# MPU-Memory.net
KiCad netlist of a schematic drawn in Altium Designer
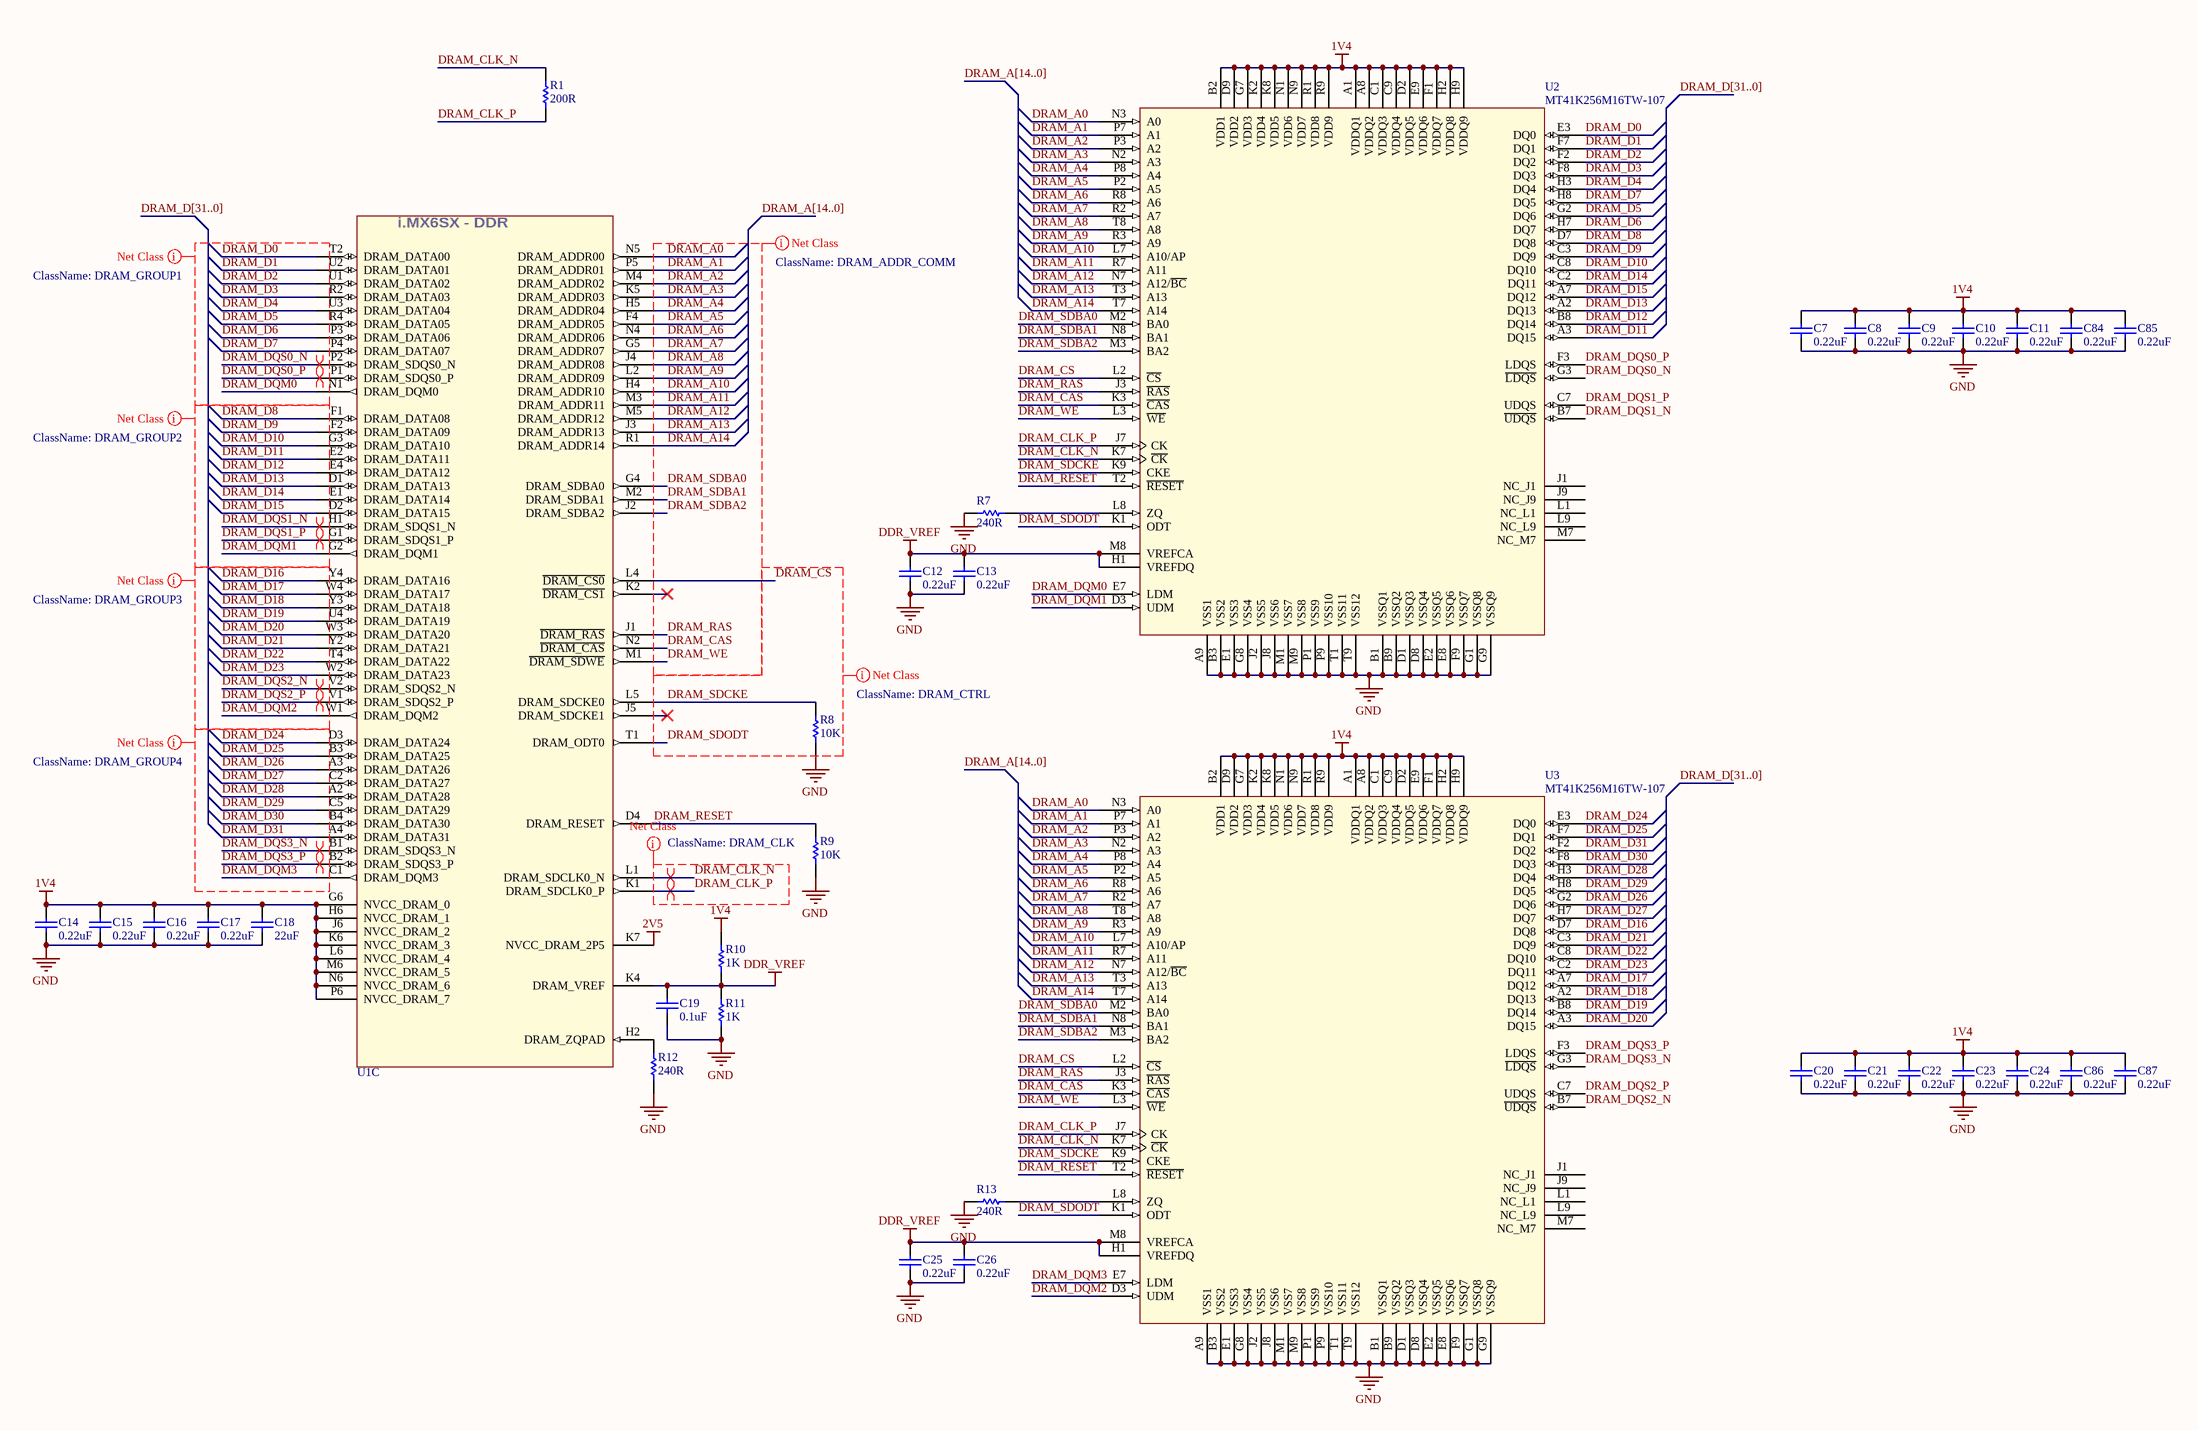
[diagram p0: MPU-Memory.SchDoc]

(export (version "E")
  (design (tool "Eeschema 10.0.6"))
  (components
    (comp (ref "C7")
      (value "0.22uF")
      (footprint "C0402[1005X55]")
      (description "0.22uF 6.3V 10% 0402 (1005 Metric)")
      (fields (field (name "PARTNUMBER") "JMK105BJ224KV-F") (field (name "MANUFACTURER") "Taiyo Yuden"))
      (libsource (lib "Capacitors") (part "CAP_0.22uF_6.3V_0402_10%"))
    )
    (comp (ref "C8")
      (value "0.22uF")
      (footprint "C0402[1005X55]")
      (description "0.22uF 6.3V 10% 0402 (1005 Metric)")
      (fields (field (name "PARTNUMBER") "JMK105BJ224KV-F") (field (name "MANUFACTURER") "Taiyo Yuden"))
      (libsource (lib "Capacitors") (part "CAP_0.22uF_6.3V_0402_10%"))
    )
    (comp (ref "C9")
      (value "0.22uF")
      (footprint "C0402[1005X55]")
      (description "0.22uF 6.3V 10% 0402 (1005 Metric)")
      (fields (field (name "PARTNUMBER") "JMK105BJ224KV-F") (field (name "MANUFACTURER") "Taiyo Yuden"))
      (libsource (lib "Capacitors") (part "CAP_0.22uF_6.3V_0402_10%"))
    )
    (comp (ref "C10")
      (value "0.22uF")
      (footprint "C0402[1005X55]")
      (description "0.22uF 6.3V 10% 0402 (1005 Metric)")
      (fields (field (name "PARTNUMBER") "JMK105BJ224KV-F") (field (name "MANUFACTURER") "Taiyo Yuden"))
      (libsource (lib "Capacitors") (part "CAP_0.22uF_6.3V_0402_10%"))
    )
    (comp (ref "C11")
      (value "0.22uF")
      (footprint "C0402[1005X55]")
      (description "0.22uF 6.3V 10% 0402 (1005 Metric)")
      (fields (field (name "PARTNUMBER") "JMK105BJ224KV-F") (field (name "MANUFACTURER") "Taiyo Yuden"))
      (libsource (lib "Capacitors") (part "CAP_0.22uF_6.3V_0402_10%"))
    )
    (comp (ref "C12")
      (value "0.22uF")
      (footprint "C0402[1005X55]")
      (description "0.22uF 6.3V 10% 0402 (1005 Metric)")
      (fields (field (name "PARTNUMBER") "JMK105BJ224KV-F") (field (name "MANUFACTURER") "Taiyo Yuden"))
      (libsource (lib "Capacitors") (part "CAP_0.22uF_6.3V_0402_10%"))
    )
    (comp (ref "C13")
      (value "0.22uF")
      (footprint "C0402[1005X55]")
      (description "0.22uF 6.3V 10% 0402 (1005 Metric)")
      (fields (field (name "PARTNUMBER") "JMK105BJ224KV-F") (field (name "MANUFACTURER") "Taiyo Yuden"))
      (libsource (lib "Capacitors") (part "CAP_0.22uF_6.3V_0402_10%"))
    )
    (comp (ref "C14")
      (value "0.22uF")
      (footprint "C0402[1005X55]")
      (description "0.22uF 6.3V 10% 0402 (1005 Metric)")
      (fields (field (name "PARTNUMBER") "JMK105BJ224KV-F") (field (name "MANUFACTURER") "Taiyo Yuden"))
      (libsource (lib "Capacitors") (part "CAP_0.22uF_6.3V_0402_10%"))
    )
    (comp (ref "C15")
      (value "0.22uF")
      (footprint "C0402[1005X55]")
      (description "0.22uF 6.3V 10% 0402 (1005 Metric)")
      (fields (field (name "PARTNUMBER") "JMK105BJ224KV-F") (field (name "MANUFACTURER") "Taiyo Yuden"))
      (libsource (lib "Capacitors") (part "CAP_0.22uF_6.3V_0402_10%"))
    )
    (comp (ref "C16")
      (value "0.22uF")
      (footprint "C0402[1005X55]")
      (description "0.22uF 6.3V 10% 0402 (1005 Metric)")
      (fields (field (name "PARTNUMBER") "JMK105BJ224KV-F") (field (name "MANUFACTURER") "Taiyo Yuden"))
      (libsource (lib "Capacitors") (part "CAP_0.22uF_6.3V_0402_10%"))
    )
    (comp (ref "C17")
      (value "0.22uF")
      (footprint "C0402[1005X55]")
      (description "0.22uF 6.3V 10% 0402 (1005 Metric)")
      (fields (field (name "PARTNUMBER") "JMK105BJ224KV-F") (field (name "MANUFACTURER") "Taiyo Yuden"))
      (libsource (lib "Capacitors") (part "CAP_0.22uF_6.3V_0402_10%"))
    )
    (comp (ref "C18")
      (value "22uF")
      (footprint "C0603[1608X92]")
      (description "22uF 6.3V 10% 0603 (1608 Metric)")
      (fields (field (name "PARTNUMBER") "GRT188R60J226ME13D") (field (name "MANUFACTURER") "Murata"))
      (libsource (lib "Capacitors") (part "CAP_22uF_6.3V_0603_10%"))
    )
    (comp (ref "C19")
      (value "0.1uF")
      (footprint "C0402[1005X55]")
      (description "0.1uF 6.3V 10% 0402 (1005 Metric)")
      (fields (field (name "PARTNUMBER") "GRM155R70J104KA01D") (field (name "MANUFACTURER") "Murata"))
      (libsource (lib "Capacitors") (part "CAP_0.1uF_6.3V_0402_10%"))
    )
    (comp (ref "C20")
      (value "0.22uF")
      (footprint "C0402[1005X55]")
      (description "0.22uF 6.3V 10% 0402 (1005 Metric)")
      (fields (field (name "PARTNUMBER") "JMK105BJ224KV-F") (field (name "MANUFACTURER") "Taiyo Yuden"))
      (libsource (lib "Capacitors") (part "CAP_0.22uF_6.3V_0402_10%"))
    )
    (comp (ref "C21")
      (value "0.22uF")
      (footprint "C0402[1005X55]")
      (description "0.22uF 6.3V 10% 0402 (1005 Metric)")
      (fields (field (name "PARTNUMBER") "JMK105BJ224KV-F") (field (name "MANUFACTURER") "Taiyo Yuden"))
      (libsource (lib "Capacitors") (part "CAP_0.22uF_6.3V_0402_10%"))
    )
    (comp (ref "C22")
      (value "0.22uF")
      (footprint "C0402[1005X55]")
      (description "0.22uF 6.3V 10% 0402 (1005 Metric)")
      (fields (field (name "PARTNUMBER") "JMK105BJ224KV-F") (field (name "MANUFACTURER") "Taiyo Yuden"))
      (libsource (lib "Capacitors") (part "CAP_0.22uF_6.3V_0402_10%"))
    )
    (comp (ref "C23")
      (value "0.22uF")
      (footprint "C0402[1005X55]")
      (description "0.22uF 6.3V 10% 0402 (1005 Metric)")
      (fields (field (name "PARTNUMBER") "JMK105BJ224KV-F") (field (name "MANUFACTURER") "Taiyo Yuden"))
      (libsource (lib "Capacitors") (part "CAP_0.22uF_6.3V_0402_10%"))
    )
    (comp (ref "C24")
      (value "0.22uF")
      (footprint "C0402[1005X55]")
      (description "0.22uF 6.3V 10% 0402 (1005 Metric)")
      (fields (field (name "PARTNUMBER") "JMK105BJ224KV-F") (field (name "MANUFACTURER") "Taiyo Yuden"))
      (libsource (lib "Capacitors") (part "CAP_0.22uF_6.3V_0402_10%"))
    )
    (comp (ref "C25")
      (value "0.22uF")
      (footprint "C0402[1005X55]")
      (description "0.22uF 6.3V 10% 0402 (1005 Metric)")
      (fields (field (name "PARTNUMBER") "JMK105BJ224KV-F") (field (name "MANUFACTURER") "Taiyo Yuden"))
      (libsource (lib "Capacitors") (part "CAP_0.22uF_6.3V_0402_10%"))
    )
    (comp (ref "C26")
      (value "0.22uF")
      (footprint "C0402[1005X55]")
      (description "0.22uF 6.3V 10% 0402 (1005 Metric)")
      (fields (field (name "PARTNUMBER") "JMK105BJ224KV-F") (field (name "MANUFACTURER") "Taiyo Yuden"))
      (libsource (lib "Capacitors") (part "CAP_0.22uF_6.3V_0402_10%"))
    )
    (comp (ref "C84")
      (value "0.22uF")
      (footprint "C0402[1005X55]")
      (description "0.22uF 6.3V 10% 0402 (1005 Metric)")
      (fields (field (name "PARTNUMBER") "JMK105BJ224KV-F") (field (name "MANUFACTURER") "Taiyo Yuden"))
      (libsource (lib "Capacitors") (part "CAP_0.22uF_6.3V_0402_10%"))
    )
    (comp (ref "C85")
      (value "0.22uF")
      (footprint "C0402[1005X55]")
      (description "0.22uF 6.3V 10% 0402 (1005 Metric)")
      (fields (field (name "PARTNUMBER") "JMK105BJ224KV-F") (field (name "MANUFACTURER") "Taiyo Yuden"))
      (libsource (lib "Capacitors") (part "CAP_0.22uF_6.3V_0402_10%"))
    )
    (comp (ref "C86")
      (value "0.22uF")
      (footprint "C0402[1005X55]")
      (description "0.22uF 6.3V 10% 0402 (1005 Metric)")
      (fields (field (name "PARTNUMBER") "JMK105BJ224KV-F") (field (name "MANUFACTURER") "Taiyo Yuden"))
      (libsource (lib "Capacitors") (part "CAP_0.22uF_6.3V_0402_10%"))
    )
    (comp (ref "C87")
      (value "0.22uF")
      (footprint "C0402[1005X55]")
      (description "0.22uF 6.3V 10% 0402 (1005 Metric)")
      (fields (field (name "PARTNUMBER") "JMK105BJ224KV-F") (field (name "MANUFACTURER") "Taiyo Yuden"))
      (libsource (lib "Capacitors") (part "CAP_0.22uF_6.3V_0402_10%"))
    )
    (comp (ref "R1")
      (value "200R")
      (footprint "R0402[1005]")
      (description "200R 0.063W 1% 0402 (1005 Metric)")
      (fields (field (name "MANUFACTURER") "KOA Speer") (field (name "PARTNUMBER") "RK73H1ETTP2000F"))
      (libsource (lib "Resistors") (part "RES_200R_0402_1%"))
    )
    (comp (ref "R7")
      (value "240R")
      (footprint "R0402[1005]")
      (description "240R 0.063W 1% 0402 (1005 Metric)")
      (fields (field (name "MANUFACTURER") "KOA Speer") (field (name "PARTNUMBER") "RK73H1ETTP2400F"))
      (libsource (lib "Resistors") (part "RES_240R_0402_1%"))
    )
    (comp (ref "R8")
      (value "10K")
      (footprint "R0402[1005]")
      (description "10K 0.063W 1% 0402 (1005 Metric)")
      (fields (field (name "MANUFACTURER") "KOA Speer") (field (name "PARTNUMBER") "RK73H1ETTP1002F"))
      (libsource (lib "Resistors") (part "RES_10K_0402_1%"))
    )
    (comp (ref "R9")
      (value "10K")
      (footprint "R0402[1005]")
      (description "10K 0.063W 1% 0402 (1005 Metric)")
      (fields (field (name "MANUFACTURER") "KOA Speer") (field (name "PARTNUMBER") "RK73H1ETTP1002F"))
      (libsource (lib "Resistors") (part "RES_10K_0402_1%"))
    )
    (comp (ref "R10")
      (value "1K")
      (footprint "R0402[1005]")
      (description "1K 0.063W 1% 0402 (1005 Metric)")
      (fields (field (name "MANUFACTURER") "KOA Speer") (field (name "PARTNUMBER") "RK73H1ETTP1001F"))
      (libsource (lib "Resistors") (part "RES_1K_0402_1%"))
    )
    (comp (ref "R11")
      (value "1K")
      (footprint "R0402[1005]")
      (description "1K 0.063W 1% 0402 (1005 Metric)")
      (fields (field (name "MANUFACTURER") "KOA Speer") (field (name "PARTNUMBER") "RK73H1ETTP1001F"))
      (libsource (lib "Resistors") (part "RES_1K_0402_1%"))
    )
    (comp (ref "R12")
      (value "240R")
      (footprint "R0402[1005]")
      (description "240R 0.063W 1% 0402 (1005 Metric)")
      (fields (field (name "MANUFACTURER") "KOA Speer") (field (name "PARTNUMBER") "RK73H1ETTP2400F"))
      (libsource (lib "Resistors") (part "RES_240R_0402_1%"))
    )
    (comp (ref "R13")
      (value "240R")
      (footprint "R0402[1005]")
      (description "240R 0.063W 1% 0402 (1005 Metric)")
      (fields (field (name "MANUFACTURER") "KOA Speer") (field (name "PARTNUMBER") "RK73H1ETTP2400F"))
      (libsource (lib "Resistors") (part "RES_240R_0402_1%"))
    )
    (comp (ref "U1")
      (value "MCIMX6X3EVO10AB")
      (footprint "BGA-400")
      (description "IC MPU I.MX6SX 1GHZ 400MAPBGA")
      (fields (field (name "MANUFACTURER") "NXP"))
      (libsource (lib "ICs") (part "MCIMX6X3EVO10AB"))
    )
    (comp (ref "U2")
      (value "MT41K256M16TW-107")
      (footprint "BGA-96")
      (description "IC SDRAM 4GBIT 933MHZ 96FBGA")
      (fields (field (name "MANUFACTURER") "Micron Technology"))
      (libsource (lib "ICs") (part "MT41K256M16TW-107"))
    )
    (comp (ref "U3")
      (value "MT41K256M16TW-107")
      (footprint "BGA-96")
      (description "IC SDRAM 4GBIT 933MHZ 96FBGA")
      (fields (field (name "MANUFACTURER") "Micron Technology"))
      (libsource (lib "ICs") (part "MT41K256M16TW-107"))
    )
  )
  (nets
    (net (code "1") (name "/DRAM_A0") (class "Default")
      (node (ref "U1") (pin "N5") (pinfunction "DRAM_ADDR00_N5") (pintype "output"))
      (node (ref "U2") (pin "N3") (pinfunction "A0_N3") (pintype "input"))
      (node (ref "U3") (pin "N3") (pinfunction "A0_N3") (pintype "input"))
    )
    (net (code "2") (name "/DRAM_A1") (class "Default")
      (node (ref "U1") (pin "P5") (pinfunction "DRAM_ADDR01_P5") (pintype "output"))
      (node (ref "U2") (pin "P7") (pinfunction "A1_P7") (pintype "input"))
      (node (ref "U3") (pin "P7") (pinfunction "A1_P7") (pintype "input"))
    )
    (net (code "3") (name "/DRAM_A2") (class "Default")
      (node (ref "U1") (pin "M4") (pinfunction "DRAM_ADDR02_M4") (pintype "output"))
      (node (ref "U2") (pin "P3") (pinfunction "A2_P3") (pintype "input"))
      (node (ref "U3") (pin "P3") (pinfunction "A2_P3") (pintype "input"))
    )
    (net (code "4") (name "/DRAM_A3") (class "Default")
      (node (ref "U1") (pin "K5") (pinfunction "DRAM_ADDR03_K5") (pintype "output"))
      (node (ref "U2") (pin "N2") (pinfunction "A3_N2") (pintype "input"))
      (node (ref "U3") (pin "N2") (pinfunction "A3_N2") (pintype "input"))
    )
    (net (code "5") (name "/DRAM_A4") (class "Default")
      (node (ref "U1") (pin "H5") (pinfunction "DRAM_ADDR04_H5") (pintype "output"))
      (node (ref "U2") (pin "P8") (pinfunction "A4_P8") (pintype "input"))
      (node (ref "U3") (pin "P8") (pinfunction "A4_P8") (pintype "input"))
    )
    (net (code "6") (name "/DRAM_A5") (class "Default")
      (node (ref "U1") (pin "F4") (pinfunction "DRAM_ADDR05_F4") (pintype "output"))
      (node (ref "U2") (pin "P2") (pinfunction "A5_P2") (pintype "input"))
      (node (ref "U3") (pin "P2") (pinfunction "A5_P2") (pintype "input"))
    )
    (net (code "7") (name "/DRAM_A6") (class "Default")
      (node (ref "U1") (pin "N4") (pinfunction "DRAM_ADDR06_N4") (pintype "output"))
      (node (ref "U2") (pin "R8") (pinfunction "A6_R8") (pintype "input"))
      (node (ref "U3") (pin "R8") (pinfunction "A6_R8") (pintype "input"))
    )
    (net (code "8") (name "/DRAM_A7") (class "Default")
      (node (ref "U1") (pin "G5") (pinfunction "DRAM_ADDR07_G5") (pintype "output"))
      (node (ref "U2") (pin "R2") (pinfunction "A7_R2") (pintype "input"))
      (node (ref "U3") (pin "R2") (pinfunction "A7_R2") (pintype "input"))
    )
    (net (code "9") (name "/DRAM_A8") (class "Default")
      (node (ref "U1") (pin "J4") (pinfunction "DRAM_ADDR08_J4") (pintype "output"))
      (node (ref "U2") (pin "T8") (pinfunction "A8_T8") (pintype "input"))
      (node (ref "U3") (pin "T8") (pinfunction "A8_T8") (pintype "input"))
    )
    (net (code "10") (name "/DRAM_A9") (class "Default")
      (node (ref "U1") (pin "L2") (pinfunction "DRAM_ADDR09_L2") (pintype "output"))
      (node (ref "U2") (pin "R3") (pinfunction "A9_R3") (pintype "input"))
      (node (ref "U3") (pin "R3") (pinfunction "A9_R3") (pintype "input"))
    )
    (net (code "11") (name "/DRAM_A10") (class "Default")
      (node (ref "U1") (pin "H4") (pinfunction "DRAM_ADDR10_H4") (pintype "output"))
      (node (ref "U2") (pin "L7") (pinfunction "A10/AP_L7") (pintype "input"))
      (node (ref "U3") (pin "L7") (pinfunction "A10/AP_L7") (pintype "input"))
    )
    (net (code "12") (name "/DRAM_A11") (class "Default")
      (node (ref "U1") (pin "M3") (pinfunction "DRAM_ADDR11_M3") (pintype "output"))
      (node (ref "U2") (pin "R7") (pinfunction "A11_R7") (pintype "input"))
      (node (ref "U3") (pin "R7") (pinfunction "A11_R7") (pintype "input"))
    )
    (net (code "13") (name "/DRAM_A12") (class "Default")
      (node (ref "U1") (pin "M5") (pinfunction "DRAM_ADDR12_M5") (pintype "output"))
      (node (ref "U2") (pin "N7") (pinfunction "A12/~{BC}_N7") (pintype "input"))
      (node (ref "U3") (pin "N7") (pinfunction "A12/~{BC}_N7") (pintype "input"))
    )
    (net (code "14") (name "/DRAM_A13") (class "Default")
      (node (ref "U1") (pin "J3") (pinfunction "DRAM_ADDR13_J3") (pintype "output"))
      (node (ref "U2") (pin "T3") (pinfunction "A13_T3") (pintype "input"))
      (node (ref "U3") (pin "T3") (pinfunction "A13_T3") (pintype "input"))
    )
    (net (code "15") (name "/DRAM_A14") (class "Default")
      (node (ref "U1") (pin "R1") (pinfunction "DRAM_ADDR14_R1") (pintype "output"))
      (node (ref "U2") (pin "T7") (pinfunction "A14_T7") (pintype "input"))
      (node (ref "U3") (pin "T7") (pinfunction "A14_T7") (pintype "input"))
    )
    (net (code "17") (name "/DRAM_CAS") (class "Default")
      (node (ref "U1") (pin "N2") (pinfunction "~{DRAM_CAS}_N2") (pintype "output"))
      (node (ref "U2") (pin "K3") (pinfunction "~{CAS}_K3") (pintype "input"))
      (node (ref "U3") (pin "K3") (pinfunction "~{CAS}_K3") (pintype "input"))
    )
    (net (code "18") (name "/DRAM_CLK_N") (class "Default")
      (node (ref "R1") (pin "2") (pinfunction "2_2") (pintype "passive"))
      (node (ref "U1") (pin "L1") (pinfunction "DRAM_SDCLK0_N_L1") (pintype "output"))
      (node (ref "U2") (pin "K7") (pinfunction "~{CK}_K7") (pintype "input"))
      (node (ref "U3") (pin "K7") (pinfunction "~{CK}_K7") (pintype "input"))
    )
    (net (code "19") (name "/DRAM_CLK_P") (class "Default")
      (node (ref "R1") (pin "1") (pinfunction "1_1") (pintype "passive"))
      (node (ref "U1") (pin "K1") (pinfunction "DRAM_SDCLK0_P_K1") (pintype "output"))
      (node (ref "U2") (pin "J7") (pinfunction "CK_J7") (pintype "input"))
      (node (ref "U3") (pin "J7") (pinfunction "CK_J7") (pintype "input"))
    )
    (net (code "20") (name "/DRAM_CS") (class "Default")
      (node (ref "U1") (pin "L4") (pinfunction "~{DRAM_CS0}_L4") (pintype "output"))
      (node (ref "U2") (pin "L2") (pinfunction "~{CS}_L2") (pintype "input"))
      (node (ref "U3") (pin "L2") (pinfunction "~{CS}_L2") (pintype "input"))
    )
    (net (code "21") (name "/DRAM_D0") (class "Default")
      (node (ref "U1") (pin "T2") (pinfunction "DRAM_DATA00_T2") (pintype "bidirectional"))
      (node (ref "U2") (pin "E3") (pinfunction "DQ0_E3") (pintype "bidirectional"))
    )
    (net (code "22") (name "/DRAM_D1") (class "Default")
      (node (ref "U1") (pin "U2") (pinfunction "DRAM_DATA01_U2") (pintype "bidirectional"))
      (node (ref "U2") (pin "F7") (pinfunction "DQ1_F7") (pintype "bidirectional"))
    )
    (net (code "23") (name "/DRAM_D2") (class "Default")
      (node (ref "U1") (pin "U1") (pinfunction "DRAM_DATA02_U1") (pintype "bidirectional"))
      (node (ref "U2") (pin "F2") (pinfunction "DQ2_F2") (pintype "bidirectional"))
    )
    (net (code "24") (name "/DRAM_D3") (class "Default")
      (node (ref "U1") (pin "R2") (pinfunction "DRAM_DATA03_R2") (pintype "bidirectional"))
      (node (ref "U2") (pin "F8") (pinfunction "DQ3_F8") (pintype "bidirectional"))
    )
    (net (code "25") (name "/DRAM_D4") (class "Default")
      (node (ref "U1") (pin "U3") (pinfunction "DRAM_DATA04_U3") (pintype "bidirectional"))
      (node (ref "U2") (pin "H3") (pinfunction "DQ4_H3") (pintype "bidirectional"))
    )
    (net (code "26") (name "/DRAM_D5") (class "Default")
      (node (ref "U1") (pin "R4") (pinfunction "DRAM_DATA05_R4") (pintype "bidirectional"))
      (node (ref "U2") (pin "G2") (pinfunction "DQ6_G2") (pintype "bidirectional"))
    )
    (net (code "27") (name "/DRAM_D6") (class "Default")
      (node (ref "U1") (pin "P3") (pinfunction "DRAM_DATA06_P3") (pintype "bidirectional"))
      (node (ref "U2") (pin "H7") (pinfunction "DQ7_H7") (pintype "bidirectional"))
    )
    (net (code "28") (name "/DRAM_D7") (class "Default")
      (node (ref "U1") (pin "P4") (pinfunction "DRAM_DATA07_P4") (pintype "bidirectional"))
      (node (ref "U2") (pin "H8") (pinfunction "DQ5_H8") (pintype "bidirectional"))
    )
    (net (code "29") (name "/DRAM_D8") (class "Default")
      (node (ref "U1") (pin "F1") (pinfunction "DRAM_DATA08_F1") (pintype "bidirectional"))
      (node (ref "U2") (pin "D7") (pinfunction "DQ8_D7") (pintype "bidirectional"))
    )
    (net (code "30") (name "/DRAM_D9") (class "Default")
      (node (ref "U1") (pin "F2") (pinfunction "DRAM_DATA09_F2") (pintype "bidirectional"))
      (node (ref "U2") (pin "C3") (pinfunction "DQ9_C3") (pintype "bidirectional"))
    )
    (net (code "31") (name "/DRAM_D10") (class "Default")
      (node (ref "U1") (pin "G3") (pinfunction "DRAM_DATA10_G3") (pintype "bidirectional"))
      (node (ref "U2") (pin "C8") (pinfunction "DQ10_C8") (pintype "bidirectional"))
    )
    (net (code "32") (name "/DRAM_D11") (class "Default")
      (node (ref "U1") (pin "E2") (pinfunction "DRAM_DATA11_E2") (pintype "bidirectional"))
      (node (ref "U2") (pin "A3") (pinfunction "DQ15_A3") (pintype "bidirectional"))
    )
    (net (code "33") (name "/DRAM_D12") (class "Default")
      (node (ref "U1") (pin "E4") (pinfunction "DRAM_DATA12_E4") (pintype "bidirectional"))
      (node (ref "U2") (pin "B8") (pinfunction "DQ14_B8") (pintype "bidirectional"))
    )
    (net (code "34") (name "/DRAM_D13") (class "Default")
      (node (ref "U1") (pin "D1") (pinfunction "DRAM_DATA13_D1") (pintype "bidirectional"))
      (node (ref "U2") (pin "A2") (pinfunction "DQ13_A2") (pintype "bidirectional"))
    )
    (net (code "35") (name "/DRAM_D14") (class "Default")
      (node (ref "U1") (pin "E1") (pinfunction "DRAM_DATA14_E1") (pintype "bidirectional"))
      (node (ref "U2") (pin "C2") (pinfunction "DQ11_C2") (pintype "bidirectional"))
    )
    (net (code "36") (name "/DRAM_D15") (class "Default")
      (node (ref "U1") (pin "D2") (pinfunction "DRAM_DATA15_D2") (pintype "bidirectional"))
      (node (ref "U2") (pin "A7") (pinfunction "DQ12_A7") (pintype "bidirectional"))
    )
    (net (code "37") (name "/DRAM_D16") (class "Default")
      (node (ref "U1") (pin "Y4") (pinfunction "DRAM_DATA16_Y4") (pintype "bidirectional"))
      (node (ref "U3") (pin "D7") (pinfunction "DQ8_D7") (pintype "bidirectional"))
    )
    (net (code "38") (name "/DRAM_D17") (class "Default")
      (node (ref "U1") (pin "W4") (pinfunction "DRAM_DATA17_W4") (pintype "bidirectional"))
      (node (ref "U3") (pin "A7") (pinfunction "DQ12_A7") (pintype "bidirectional"))
    )
    (net (code "39") (name "/DRAM_D18") (class "Default")
      (node (ref "U1") (pin "Y3") (pinfunction "DRAM_DATA18_Y3") (pintype "bidirectional"))
      (node (ref "U3") (pin "A2") (pinfunction "DQ13_A2") (pintype "bidirectional"))
    )
    (net (code "40") (name "/DRAM_D19") (class "Default")
      (node (ref "U1") (pin "U4") (pinfunction "DRAM_DATA19_U4") (pintype "bidirectional"))
      (node (ref "U3") (pin "B8") (pinfunction "DQ14_B8") (pintype "bidirectional"))
    )
    (net (code "41") (name "/DRAM_D20") (class "Default")
      (node (ref "U1") (pin "W3") (pinfunction "DRAM_DATA20_W3") (pintype "bidirectional"))
      (node (ref "U3") (pin "A3") (pinfunction "DQ15_A3") (pintype "bidirectional"))
    )
    (net (code "42") (name "/DRAM_D21") (class "Default")
      (node (ref "U1") (pin "Y2") (pinfunction "DRAM_DATA21_Y2") (pintype "bidirectional"))
      (node (ref "U3") (pin "C3") (pinfunction "DQ9_C3") (pintype "bidirectional"))
    )
    (net (code "43") (name "/DRAM_D22") (class "Default")
      (node (ref "U1") (pin "T4") (pinfunction "DRAM_DATA22_T4") (pintype "bidirectional"))
      (node (ref "U3") (pin "C8") (pinfunction "DQ10_C8") (pintype "bidirectional"))
    )
    (net (code "44") (name "/DRAM_D23") (class "Default")
      (node (ref "U1") (pin "W2") (pinfunction "DRAM_DATA23_W2") (pintype "bidirectional"))
      (node (ref "U3") (pin "C2") (pinfunction "DQ11_C2") (pintype "bidirectional"))
    )
    (net (code "45") (name "/DRAM_D24") (class "Default")
      (node (ref "U1") (pin "D3") (pinfunction "DRAM_DATA24_D3") (pintype "bidirectional"))
      (node (ref "U3") (pin "E3") (pinfunction "DQ0_E3") (pintype "bidirectional"))
    )
    (net (code "46") (name "/DRAM_D25") (class "Default")
      (node (ref "U1") (pin "B3") (pinfunction "DRAM_DATA25_B3") (pintype "bidirectional"))
      (node (ref "U3") (pin "F7") (pinfunction "DQ1_F7") (pintype "bidirectional"))
    )
    (net (code "47") (name "/DRAM_D26") (class "Default")
      (node (ref "U1") (pin "A3") (pinfunction "DRAM_DATA26_A3") (pintype "bidirectional"))
      (node (ref "U3") (pin "G2") (pinfunction "DQ6_G2") (pintype "bidirectional"))
    )
    (net (code "48") (name "/DRAM_D27") (class "Default")
      (node (ref "U1") (pin "C2") (pinfunction "DRAM_DATA27_C2") (pintype "bidirectional"))
      (node (ref "U3") (pin "H7") (pinfunction "DQ7_H7") (pintype "bidirectional"))
    )
    (net (code "49") (name "/DRAM_D28") (class "Default")
      (node (ref "U1") (pin "A2") (pinfunction "DRAM_DATA28_A2") (pintype "bidirectional"))
      (node (ref "U3") (pin "H3") (pinfunction "DQ4_H3") (pintype "bidirectional"))
    )
    (net (code "50") (name "/DRAM_D29") (class "Default")
      (node (ref "U1") (pin "C5") (pinfunction "DRAM_DATA29_C5") (pintype "bidirectional"))
      (node (ref "U3") (pin "H8") (pinfunction "DQ5_H8") (pintype "bidirectional"))
    )
    (net (code "51") (name "/DRAM_D30") (class "Default")
      (node (ref "U1") (pin "B4") (pinfunction "DRAM_DATA30_B4") (pintype "bidirectional"))
      (node (ref "U3") (pin "F8") (pinfunction "DQ3_F8") (pintype "bidirectional"))
    )
    (net (code "52") (name "/DRAM_D31") (class "Default")
      (node (ref "U1") (pin "A4") (pinfunction "DRAM_DATA31_A4") (pintype "bidirectional"))
      (node (ref "U3") (pin "F2") (pinfunction "DQ2_F2") (pintype "bidirectional"))
    )
    (net (code "53") (name "/DRAM_DQM0") (class "Default")
      (node (ref "U1") (pin "N1") (pinfunction "DRAM_DQM0_N1") (pintype "output"))
      (node (ref "U2") (pin "E7") (pinfunction "LDM_E7") (pintype "input"))
    )
    (net (code "54") (name "/DRAM_DQM1") (class "Default")
      (node (ref "U1") (pin "G2") (pinfunction "DRAM_DQM1_G2") (pintype "output"))
      (node (ref "U2") (pin "D3") (pinfunction "UDM_D3") (pintype "input"))
    )
    (net (code "55") (name "/DRAM_DQM2") (class "Default")
      (node (ref "U1") (pin "W1") (pinfunction "DRAM_DQM2_W1") (pintype "output"))
      (node (ref "U3") (pin "D3") (pinfunction "UDM_D3") (pintype "input"))
    )
    (net (code "56") (name "/DRAM_DQM3") (class "Default")
      (node (ref "U1") (pin "C1") (pinfunction "DRAM_DQM3_C1") (pintype "output"))
      (node (ref "U3") (pin "E7") (pinfunction "LDM_E7") (pintype "input"))
    )
    (net (code "57") (name "/DRAM_DQS0_N") (class "Default")
      (node (ref "U1") (pin "P2") (pinfunction "DRAM_SDQS0_N_P2") (pintype "bidirectional"))
      (node (ref "U2") (pin "G3") (pinfunction "~{LDQS}_G3") (pintype "bidirectional"))
    )
    (net (code "58") (name "/DRAM_DQS0_P") (class "Default")
      (node (ref "U1") (pin "P1") (pinfunction "DRAM_SDQS0_P_P1") (pintype "bidirectional"))
      (node (ref "U2") (pin "F3") (pinfunction "LDQS_F3") (pintype "bidirectional"))
    )
    (net (code "59") (name "/DRAM_DQS1_N") (class "Default")
      (node (ref "U1") (pin "H1") (pinfunction "DRAM_SDQS1_N_H1") (pintype "bidirectional"))
      (node (ref "U2") (pin "B7") (pinfunction "~{UDQS}_B7") (pintype "bidirectional"))
    )
    (net (code "60") (name "/DRAM_DQS1_P") (class "Default")
      (node (ref "U1") (pin "G1") (pinfunction "DRAM_SDQS1_P_G1") (pintype "bidirectional"))
      (node (ref "U2") (pin "C7") (pinfunction "UDQS_C7") (pintype "bidirectional"))
    )
    (net (code "61") (name "/DRAM_DQS2_N") (class "Default")
      (node (ref "U1") (pin "V2") (pinfunction "DRAM_SDQS2_N_V2") (pintype "bidirectional"))
      (node (ref "U3") (pin "B7") (pinfunction "~{UDQS}_B7") (pintype "bidirectional"))
    )
    (net (code "62") (name "/DRAM_DQS2_P") (class "Default")
      (node (ref "U1") (pin "V1") (pinfunction "DRAM_SDQS2_P_V1") (pintype "bidirectional"))
      (node (ref "U3") (pin "C7") (pinfunction "UDQS_C7") (pintype "bidirectional"))
    )
    (net (code "63") (name "/DRAM_DQS3_N") (class "Default")
      (node (ref "U1") (pin "B1") (pinfunction "DRAM_SDQS3_N_B1") (pintype "bidirectional"))
      (node (ref "U3") (pin "G3") (pinfunction "~{LDQS}_G3") (pintype "bidirectional"))
    )
    (net (code "64") (name "/DRAM_DQS3_P") (class "Default")
      (node (ref "U1") (pin "B2") (pinfunction "DRAM_SDQS3_P_B2") (pintype "bidirectional"))
      (node (ref "U3") (pin "F3") (pinfunction "LDQS_F3") (pintype "bidirectional"))
    )
    (net (code "66") (name "/DRAM_RAS") (class "Default")
      (node (ref "U1") (pin "J1") (pinfunction "~{DRAM_RAS}_J1") (pintype "output"))
      (node (ref "U2") (pin "J3") (pinfunction "~{RAS}_J3") (pintype "input"))
      (node (ref "U3") (pin "J3") (pinfunction "~{RAS}_J3") (pintype "input"))
    )
    (net (code "67") (name "/DRAM_RESET") (class "Default")
      (node (ref "R9") (pin "2") (pinfunction "2_2") (pintype "passive"))
      (node (ref "U1") (pin "D4") (pinfunction "DRAM_RESET_D4") (pintype "output"))
      (node (ref "U2") (pin "T2") (pinfunction "~{RESET}_T2") (pintype "input"))
      (node (ref "U3") (pin "T2") (pinfunction "~{RESET}_T2") (pintype "input"))
    )
    (net (code "68") (name "/DRAM_SDBA0") (class "Default")
      (node (ref "U1") (pin "G4") (pinfunction "DRAM_SDBA0_G4") (pintype "output"))
      (node (ref "U2") (pin "M2") (pinfunction "BA0_M2") (pintype "input"))
      (node (ref "U3") (pin "M2") (pinfunction "BA0_M2") (pintype "input"))
    )
    (net (code "69") (name "/DRAM_SDBA1") (class "Default")
      (node (ref "U1") (pin "M2") (pinfunction "DRAM_SDBA1_M2") (pintype "output"))
      (node (ref "U2") (pin "N8") (pinfunction "BA1_N8") (pintype "input"))
      (node (ref "U3") (pin "N8") (pinfunction "BA1_N8") (pintype "input"))
    )
    (net (code "70") (name "/DRAM_SDBA2") (class "Default")
      (node (ref "U1") (pin "J2") (pinfunction "DRAM_SDBA2_J2") (pintype "output"))
      (node (ref "U2") (pin "M3") (pinfunction "BA2_M3") (pintype "input"))
      (node (ref "U3") (pin "M3") (pinfunction "BA2_M3") (pintype "input"))
    )
    (net (code "71") (name "/DRAM_SDCKE") (class "Default")
      (node (ref "R8") (pin "2") (pinfunction "2_2") (pintype "passive"))
      (node (ref "U1") (pin "L5") (pinfunction "DRAM_SDCKE0_L5") (pintype "output"))
      (node (ref "U2") (pin "K9") (pinfunction "CKE_K9") (pintype "input"))
      (node (ref "U3") (pin "K9") (pinfunction "CKE_K9") (pintype "input"))
    )
    (net (code "72") (name "/DRAM_SDODT") (class "Default")
      (node (ref "U1") (pin "T1") (pinfunction "DRAM_ODT0_T1") (pintype "output"))
      (node (ref "U2") (pin "K1") (pinfunction "ODT_K1") (pintype "input"))
      (node (ref "U3") (pin "K1") (pinfunction "ODT_K1") (pintype "input"))
    )
    (net (code "73") (name "/DRAM_WE") (class "Default")
      (node (ref "U1") (pin "M1") (pinfunction "~{DRAM_SDWE}_M1") (pintype "output"))
      (node (ref "U2") (pin "L3") (pinfunction "~{WE}_L3") (pintype "input"))
      (node (ref "U3") (pin "L3") (pinfunction "~{WE}_L3") (pintype "input"))
    )
    (net (code "74") (name "1V4") (class "Default")
      (node (ref "C10") (pin "2") (pinfunction "2_2") (pintype "passive"))
      (node (ref "C11") (pin "2") (pinfunction "2_2") (pintype "passive"))
      (node (ref "C14") (pin "2") (pinfunction "2_2") (pintype "passive"))
      (node (ref "C15") (pin "2") (pinfunction "2_2") (pintype "passive"))
      (node (ref "C16") (pin "2") (pinfunction "2_2") (pintype "passive"))
      (node (ref "C17") (pin "2") (pinfunction "2_2") (pintype "passive"))
      (node (ref "C18") (pin "2") (pinfunction "2_2") (pintype "passive"))
      (node (ref "C20") (pin "2") (pinfunction "2_2") (pintype "passive"))
      (node (ref "C21") (pin "2") (pinfunction "2_2") (pintype "passive"))
      (node (ref "C22") (pin "2") (pinfunction "2_2") (pintype "passive"))
      (node (ref "C23") (pin "2") (pinfunction "2_2") (pintype "passive"))
      (node (ref "C24") (pin "2") (pinfunction "2_2") (pintype "passive"))
      (node (ref "C7") (pin "2") (pinfunction "2_2") (pintype "passive"))
      (node (ref "C8") (pin "2") (pinfunction "2_2") (pintype "passive"))
      (node (ref "C84") (pin "2") (pinfunction "2_2") (pintype "passive"))
      (node (ref "C85") (pin "2") (pinfunction "2_2") (pintype "passive"))
      (node (ref "C86") (pin "2") (pinfunction "2_2") (pintype "passive"))
      (node (ref "C87") (pin "2") (pinfunction "2_2") (pintype "passive"))
      (node (ref "C9") (pin "2") (pinfunction "2_2") (pintype "passive"))
      (node (ref "R10") (pin "2") (pinfunction "2_2") (pintype "passive"))
      (node (ref "U1") (pin "G6") (pinfunction "NVCC_DRAM_0_G6") (pintype "power_in"))
      (node (ref "U1") (pin "H6") (pinfunction "NVCC_DRAM_1_H6") (pintype "power_in"))
      (node (ref "U1") (pin "J6") (pinfunction "NVCC_DRAM_2_J6") (pintype "power_in"))
      (node (ref "U1") (pin "K6") (pinfunction "NVCC_DRAM_3_K6") (pintype "power_in"))
      (node (ref "U1") (pin "L6") (pinfunction "NVCC_DRAM_4_L6") (pintype "power_in"))
      (node (ref "U1") (pin "M6") (pinfunction "NVCC_DRAM_5_M6") (pintype "power_in"))
      (node (ref "U1") (pin "N6") (pinfunction "NVCC_DRAM_6_N6") (pintype "power_in"))
      (node (ref "U1") (pin "P6") (pinfunction "NVCC_DRAM_7_P6") (pintype "power_in"))
      (node (ref "U2") (pin "A1") (pinfunction "VDDQ1_A1") (pintype "power_in"))
      (node (ref "U2") (pin "A8") (pinfunction "VDDQ2_A8") (pintype "power_in"))
      (node (ref "U2") (pin "B2") (pinfunction "VDD1_B2") (pintype "power_in"))
      (node (ref "U2") (pin "C1") (pinfunction "VDDQ3_C1") (pintype "power_in"))
      (node (ref "U2") (pin "C9") (pinfunction "VDDQ4_C9") (pintype "power_in"))
      (node (ref "U2") (pin "D2") (pinfunction "VDDQ5_D2") (pintype "power_in"))
      (node (ref "U2") (pin "D9") (pinfunction "VDD2_D9") (pintype "power_in"))
      (node (ref "U2") (pin "E9") (pinfunction "VDDQ6_E9") (pintype "power_in"))
      (node (ref "U2") (pin "F1") (pinfunction "VDDQ7_F1") (pintype "power_in"))
      (node (ref "U2") (pin "G7") (pinfunction "VDD3_G7") (pintype "power_in"))
      (node (ref "U2") (pin "H2") (pinfunction "VDDQ8_H2") (pintype "power_in"))
      (node (ref "U2") (pin "H9") (pinfunction "VDDQ9_H9") (pintype "power_in"))
      (node (ref "U2") (pin "K2") (pinfunction "VDD4_K2") (pintype "power_in"))
      (node (ref "U2") (pin "K8") (pinfunction "VDD5_K8") (pintype "power_in"))
      (node (ref "U2") (pin "N1") (pinfunction "VDD6_N1") (pintype "power_in"))
      (node (ref "U2") (pin "N9") (pinfunction "VDD7_N9") (pintype "power_in"))
      (node (ref "U2") (pin "R1") (pinfunction "VDD8_R1") (pintype "power_in"))
      (node (ref "U2") (pin "R9") (pinfunction "VDD9_R9") (pintype "power_in"))
      (node (ref "U3") (pin "A1") (pinfunction "VDDQ1_A1") (pintype "power_in"))
      (node (ref "U3") (pin "A8") (pinfunction "VDDQ2_A8") (pintype "power_in"))
      (node (ref "U3") (pin "B2") (pinfunction "VDD1_B2") (pintype "power_in"))
      (node (ref "U3") (pin "C1") (pinfunction "VDDQ3_C1") (pintype "power_in"))
      (node (ref "U3") (pin "C9") (pinfunction "VDDQ4_C9") (pintype "power_in"))
      (node (ref "U3") (pin "D2") (pinfunction "VDDQ5_D2") (pintype "power_in"))
      (node (ref "U3") (pin "D9") (pinfunction "VDD2_D9") (pintype "power_in"))
      (node (ref "U3") (pin "E9") (pinfunction "VDDQ6_E9") (pintype "power_in"))
      (node (ref "U3") (pin "F1") (pinfunction "VDDQ7_F1") (pintype "power_in"))
      (node (ref "U3") (pin "G7") (pinfunction "VDD3_G7") (pintype "power_in"))
      (node (ref "U3") (pin "H2") (pinfunction "VDDQ8_H2") (pintype "power_in"))
      (node (ref "U3") (pin "H9") (pinfunction "VDDQ9_H9") (pintype "power_in"))
      (node (ref "U3") (pin "K2") (pinfunction "VDD4_K2") (pintype "power_in"))
      (node (ref "U3") (pin "K8") (pinfunction "VDD5_K8") (pintype "power_in"))
      (node (ref "U3") (pin "N1") (pinfunction "VDD6_N1") (pintype "power_in"))
      (node (ref "U3") (pin "N9") (pinfunction "VDD7_N9") (pintype "power_in"))
      (node (ref "U3") (pin "R1") (pinfunction "VDD8_R1") (pintype "power_in"))
      (node (ref "U3") (pin "R9") (pinfunction "VDD9_R9") (pintype "power_in"))
    )
    (net (code "75") (name "2V5") (class "Default")
      (node (ref "U1") (pin "K7") (pinfunction "NVCC_DRAM_2P5_K7") (pintype "power_in"))
    )
    (net (code "76") (name "DDR_VREF") (class "Default")
      (node (ref "C12") (pin "2") (pinfunction "2_2") (pintype "passive"))
      (node (ref "C13") (pin "2") (pinfunction "2_2") (pintype "passive"))
      (node (ref "C19") (pin "2") (pinfunction "2_2") (pintype "passive"))
      (node (ref "C25") (pin "2") (pinfunction "2_2") (pintype "passive"))
      (node (ref "C26") (pin "2") (pinfunction "2_2") (pintype "passive"))
      (node (ref "R10") (pin "1") (pinfunction "1_1") (pintype "passive"))
      (node (ref "R11") (pin "2") (pinfunction "2_2") (pintype "passive"))
      (node (ref "U1") (pin "K4") (pinfunction "DRAM_VREF_K4") (pintype "power_in"))
      (node (ref "U2") (pin "H1") (pinfunction "VREFDQ_H1") (pintype "power_in"))
      (node (ref "U2") (pin "M8") (pinfunction "VREFCA_M8") (pintype "power_in"))
      (node (ref "U3") (pin "H1") (pinfunction "VREFDQ_H1") (pintype "power_in"))
      (node (ref "U3") (pin "M8") (pinfunction "VREFCA_M8") (pintype "power_in"))
    )
    (net (code "77") (name "GND") (class "Default")
      (node (ref "C10") (pin "1") (pinfunction "1_1") (pintype "passive"))
      (node (ref "C11") (pin "1") (pinfunction "1_1") (pintype "passive"))
      (node (ref "C12") (pin "1") (pinfunction "1_1") (pintype "passive"))
      (node (ref "C13") (pin "1") (pinfunction "1_1") (pintype "passive"))
      (node (ref "C14") (pin "1") (pinfunction "1_1") (pintype "passive"))
      (node (ref "C15") (pin "1") (pinfunction "1_1") (pintype "passive"))
      (node (ref "C16") (pin "1") (pinfunction "1_1") (pintype "passive"))
      (node (ref "C17") (pin "1") (pinfunction "1_1") (pintype "passive"))
      (node (ref "C18") (pin "1") (pinfunction "1_1") (pintype "passive"))
      (node (ref "C19") (pin "1") (pinfunction "1_1") (pintype "passive"))
      (node (ref "C20") (pin "1") (pinfunction "1_1") (pintype "passive"))
      (node (ref "C21") (pin "1") (pinfunction "1_1") (pintype "passive"))
      (node (ref "C22") (pin "1") (pinfunction "1_1") (pintype "passive"))
      (node (ref "C23") (pin "1") (pinfunction "1_1") (pintype "passive"))
      (node (ref "C24") (pin "1") (pinfunction "1_1") (pintype "passive"))
      (node (ref "C25") (pin "1") (pinfunction "1_1") (pintype "passive"))
      (node (ref "C26") (pin "1") (pinfunction "1_1") (pintype "passive"))
      (node (ref "C7") (pin "1") (pinfunction "1_1") (pintype "passive"))
      (node (ref "C8") (pin "1") (pinfunction "1_1") (pintype "passive"))
      (node (ref "C84") (pin "1") (pinfunction "1_1") (pintype "passive"))
      (node (ref "C85") (pin "1") (pinfunction "1_1") (pintype "passive"))
      (node (ref "C86") (pin "1") (pinfunction "1_1") (pintype "passive"))
      (node (ref "C87") (pin "1") (pinfunction "1_1") (pintype "passive"))
      (node (ref "C9") (pin "1") (pinfunction "1_1") (pintype "passive"))
      (node (ref "R11") (pin "1") (pinfunction "1_1") (pintype "passive"))
      (node (ref "R12") (pin "1") (pinfunction "1_1") (pintype "passive"))
      (node (ref "R13") (pin "2") (pinfunction "2_2") (pintype "passive"))
      (node (ref "R7") (pin "2") (pinfunction "2_2") (pintype "passive"))
      (node (ref "R8") (pin "1") (pinfunction "1_1") (pintype "passive"))
      (node (ref "R9") (pin "1") (pinfunction "1_1") (pintype "passive"))
      (node (ref "U2") (pin "A9") (pinfunction "VSS1_A9") (pintype "power_in"))
      (node (ref "U2") (pin "B1") (pinfunction "VSSQ1_B1") (pintype "power_in"))
      (node (ref "U2") (pin "B3") (pinfunction "VSS2_B3") (pintype "power_in"))
      (node (ref "U2") (pin "B9") (pinfunction "VSSQ2_B9") (pintype "power_in"))
      (node (ref "U2") (pin "D1") (pinfunction "VSSQ3_D1") (pintype "power_in"))
      (node (ref "U2") (pin "D8") (pinfunction "VSSQ4_D8") (pintype "power_in"))
      (node (ref "U2") (pin "E1") (pinfunction "VSS3_E1") (pintype "power_in"))
      (node (ref "U2") (pin "E2") (pinfunction "VSSQ5_E2") (pintype "power_in"))
      (node (ref "U2") (pin "E8") (pinfunction "VSSQ6_E8") (pintype "power_in"))
      (node (ref "U2") (pin "F9") (pinfunction "VSSQ7_F9") (pintype "power_in"))
      (node (ref "U2") (pin "G1") (pinfunction "VSSQ8_G1") (pintype "power_in"))
      (node (ref "U2") (pin "G8") (pinfunction "VSS4_G8") (pintype "power_in"))
      (node (ref "U2") (pin "G9") (pinfunction "VSSQ9_G9") (pintype "power_in"))
      (node (ref "U2") (pin "J2") (pinfunction "VSS5_J2") (pintype "power_in"))
      (node (ref "U2") (pin "J8") (pinfunction "VSS6_J8") (pintype "power_in"))
      (node (ref "U2") (pin "M1") (pinfunction "VSS7_M1") (pintype "power_in"))
      (node (ref "U2") (pin "M9") (pinfunction "VSS8_M9") (pintype "power_in"))
      (node (ref "U2") (pin "P1") (pinfunction "VSS9_P1") (pintype "power_in"))
      (node (ref "U2") (pin "P9") (pinfunction "VSS10_P9") (pintype "power_in"))
      (node (ref "U2") (pin "T1") (pinfunction "VSS11_T1") (pintype "power_in"))
      (node (ref "U2") (pin "T9") (pinfunction "VSS12_T9") (pintype "power_in"))
      (node (ref "U3") (pin "A9") (pinfunction "VSS1_A9") (pintype "power_in"))
      (node (ref "U3") (pin "B1") (pinfunction "VSSQ1_B1") (pintype "power_in"))
      (node (ref "U3") (pin "B3") (pinfunction "VSS2_B3") (pintype "power_in"))
      (node (ref "U3") (pin "B9") (pinfunction "VSSQ2_B9") (pintype "power_in"))
      (node (ref "U3") (pin "D1") (pinfunction "VSSQ3_D1") (pintype "power_in"))
      (node (ref "U3") (pin "D8") (pinfunction "VSSQ4_D8") (pintype "power_in"))
      (node (ref "U3") (pin "E1") (pinfunction "VSS3_E1") (pintype "power_in"))
      (node (ref "U3") (pin "E2") (pinfunction "VSSQ5_E2") (pintype "power_in"))
      (node (ref "U3") (pin "E8") (pinfunction "VSSQ6_E8") (pintype "power_in"))
      (node (ref "U3") (pin "F9") (pinfunction "VSSQ7_F9") (pintype "power_in"))
      (node (ref "U3") (pin "G1") (pinfunction "VSSQ8_G1") (pintype "power_in"))
      (node (ref "U3") (pin "G8") (pinfunction "VSS4_G8") (pintype "power_in"))
      (node (ref "U3") (pin "G9") (pinfunction "VSSQ9_G9") (pintype "power_in"))
      (node (ref "U3") (pin "J2") (pinfunction "VSS5_J2") (pintype "power_in"))
      (node (ref "U3") (pin "J8") (pinfunction "VSS6_J8") (pintype "power_in"))
      (node (ref "U3") (pin "M1") (pinfunction "VSS7_M1") (pintype "power_in"))
      (node (ref "U3") (pin "M9") (pinfunction "VSS8_M9") (pintype "power_in"))
      (node (ref "U3") (pin "P1") (pinfunction "VSS9_P1") (pintype "power_in"))
      (node (ref "U3") (pin "P9") (pinfunction "VSS10_P9") (pintype "power_in"))
      (node (ref "U3") (pin "T1") (pinfunction "VSS11_T1") (pintype "power_in"))
      (node (ref "U3") (pin "T9") (pinfunction "VSS12_T9") (pintype "power_in"))
    )
    (net (code "78") (name "Net-(U1C-DRAM_ZQPAD)") (class "Default")
      (node (ref "R12") (pin "2") (pinfunction "2_2") (pintype "passive"))
      (node (ref "U1") (pin "H2") (pinfunction "DRAM_ZQPAD_H2") (pintype "input"))
    )
    (net (code "79") (name "Net-(U2-ZQ)") (class "Default")
      (node (ref "R7") (pin "1") (pinfunction "1_1") (pintype "passive"))
      (node (ref "U2") (pin "L8") (pinfunction "ZQ_L8") (pintype "input"))
    )
    (net (code "80") (name "Net-(U3-ZQ)") (class "Default")
      (node (ref "R13") (pin "1") (pinfunction "1_1") (pintype "passive"))
      (node (ref "U3") (pin "L8") (pinfunction "ZQ_L8") (pintype "input"))
    )
    (net (code "81") (name "unconnected-(U1C-DRAM_SDCKE1-PadJ5)") (class "Default")
      (node (ref "U1") (pin "J5") (pinfunction "DRAM_SDCKE1_J5") (pintype "output+no_connect"))
    )
    (net (code "82") (name "unconnected-(U1C-~{DRAM_CS1}-PadK2)") (class "Default")
      (node (ref "U1") (pin "K2") (pinfunction "~{DRAM_CS1}_K2") (pintype "output+no_connect"))
    )
    (net (code "83") (name "unconnected-(U2-NC_J1-PadJ1)") (class "Default")
      (node (ref "U2") (pin "J1") (pinfunction "NC_J1_J1") (pintype "passive"))
    )
    (net (code "84") (name "unconnected-(U2-NC_J9-PadJ9)") (class "Default")
      (node (ref "U2") (pin "J9") (pinfunction "NC_J9_J9") (pintype "passive"))
    )
    (net (code "85") (name "unconnected-(U2-NC_L1-PadL1)") (class "Default")
      (node (ref "U2") (pin "L1") (pinfunction "NC_L1_L1") (pintype "passive"))
    )
    (net (code "86") (name "unconnected-(U2-NC_L9-PadL9)") (class "Default")
      (node (ref "U2") (pin "L9") (pinfunction "NC_L9_L9") (pintype "passive"))
    )
    (net (code "87") (name "unconnected-(U2-NC_M7-PadM7)") (class "Default")
      (node (ref "U2") (pin "M7") (pinfunction "NC_M7_M7") (pintype "passive"))
    )
    (net (code "88") (name "unconnected-(U3-NC_J1-PadJ1)") (class "Default")
      (node (ref "U3") (pin "J1") (pinfunction "NC_J1_J1") (pintype "passive"))
    )
    (net (code "89") (name "unconnected-(U3-NC_J9-PadJ9)") (class "Default")
      (node (ref "U3") (pin "J9") (pinfunction "NC_J9_J9") (pintype "passive"))
    )
    (net (code "90") (name "unconnected-(U3-NC_L1-PadL1)") (class "Default")
      (node (ref "U3") (pin "L1") (pinfunction "NC_L1_L1") (pintype "passive"))
    )
    (net (code "91") (name "unconnected-(U3-NC_L9-PadL9)") (class "Default")
      (node (ref "U3") (pin "L9") (pinfunction "NC_L9_L9") (pintype "passive"))
    )
    (net (code "92") (name "unconnected-(U3-NC_M7-PadM7)") (class "Default")
      (node (ref "U3") (pin "M7") (pinfunction "NC_M7_M7") (pintype "passive"))
    )
  )
)
